# 04_LMS7002M_Misc.net
KiCad netlist of a schematic drawn in Altium Designer
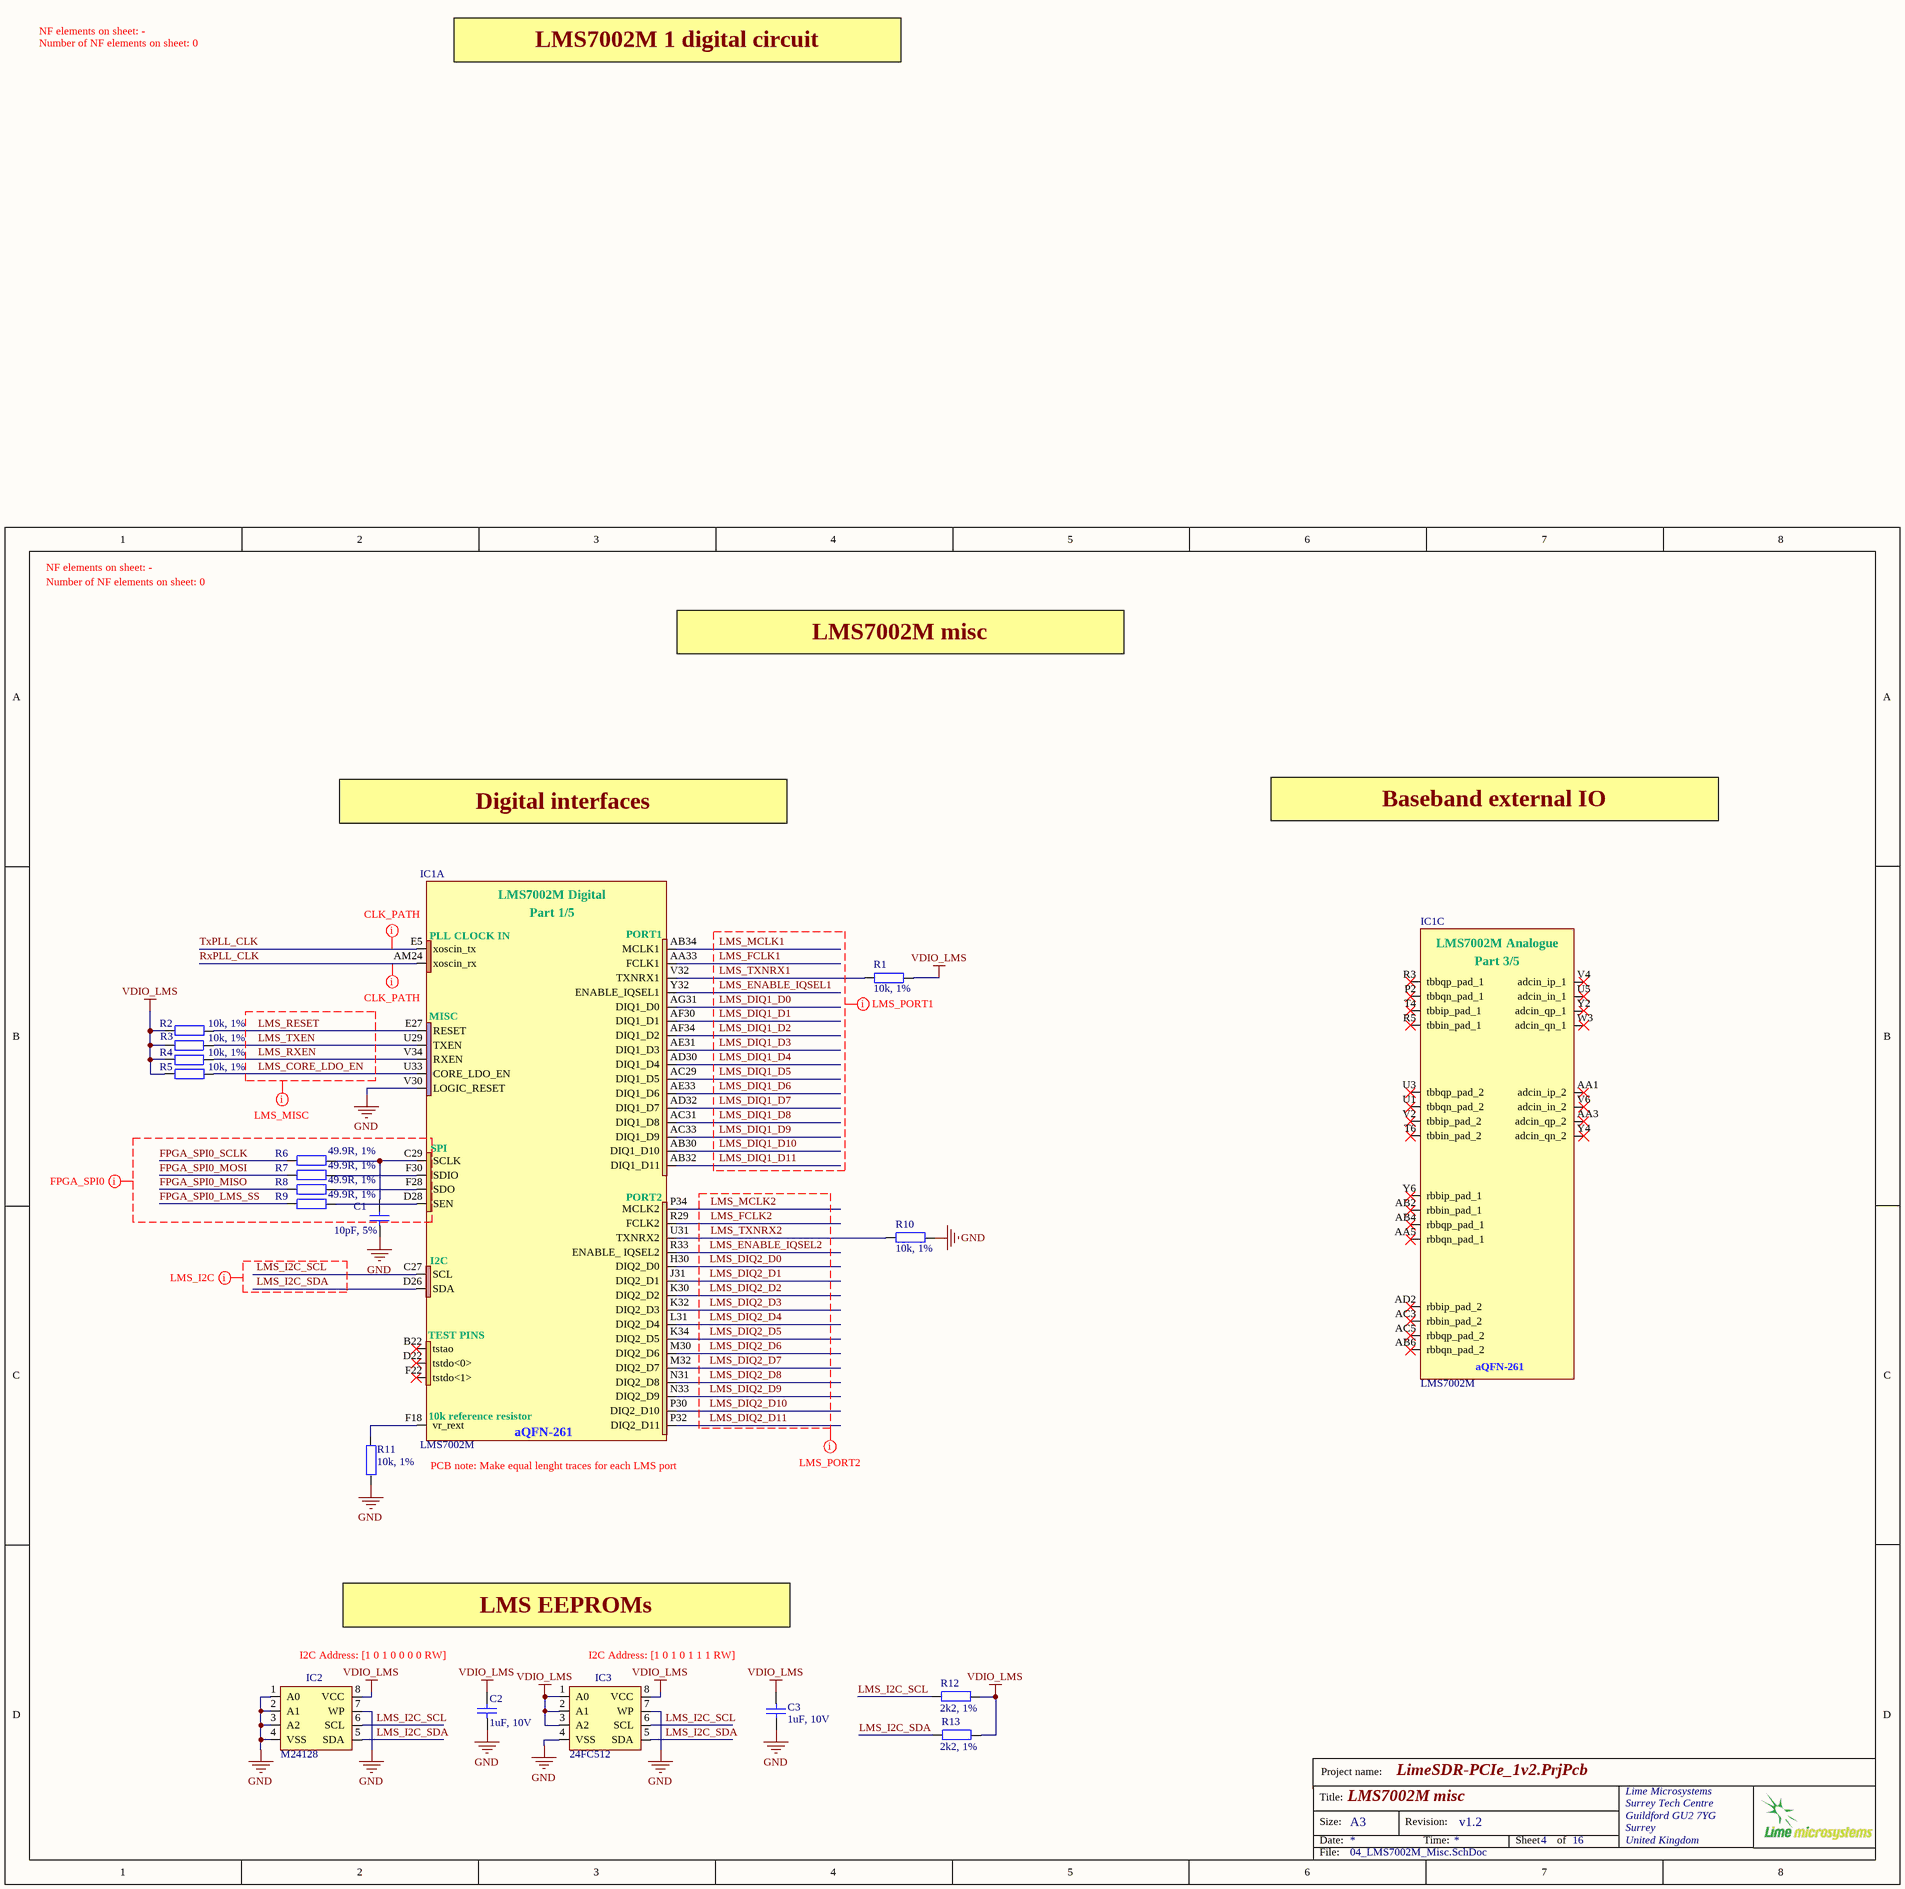
[diagram p0: 04_LMS7002M_Misc.SchDoc]

(export (version "E")
  (design (tool "Eeschema 10.0.6"))
  (components
    (comp (ref "C1")
      (value "10pF, 5%")
      (footprint "CAP0402")
      (fields (field (name "MANUFACTURER") "AVX"))
      (libsource (lib "LimeMicroAltiumLib_schLib") (part "Cap_0402"))
    )
    (comp (ref "C2")
      (value "1uF, 10V")
      (footprint "CAP0402")
      (fields (field (name "MANUFACTURER") "TDK"))
      (libsource (lib "LimeMicroAltiumLib_schLib") (part "Cap_0402"))
    )
    (comp (ref "C3")
      (value "1uF, 10V")
      (footprint "CAP0402")
      (fields (field (name "MANUFACTURER") "TDK"))
      (libsource (lib "LimeMicroAltiumLib_schLib") (part "Cap_0402"))
    )
    (comp (ref "IC1")
      (value "LMS7002M")
      (footprint "LMS7002M_v2")
      (fields (field (name "MANUFACTURER") "Lime Microsystems"))
      (libsource (lib "LimeMicroAltiumLib_schLib") (part "LMS7002M"))
    )
    (comp (ref "IC2")
      (value "M24128")
      (footprint "24FC512")
      (fields (field (name "MANUFACTURER") "STMicroelectronics"))
      (libsource (lib "LimeMicroAltiumLib_schLib") (part "24FC64F"))
    )
    (comp (ref "IC3")
      (value "24FC512")
      (footprint "24FC512")
      (fields (field (name "MANUFACTURER") "Microchip Technology"))
      (libsource (lib "LimeMicroAltiumLib_schLib") (part "24FC512"))
    )
    (comp (ref "R1")
      (value "10k, 1%")
      (footprint "RES0402")
      (fields (field (name "MANUFACTURER") "Yageo") (field (name "TOLERANCE") "±1%"))
      (libsource (lib "LimeMicroAltiumLib_schLib") (part "Res_0402"))
    )
    (comp (ref "R2")
      (value "10k, 1%")
      (footprint "RES0402")
      (fields (field (name "MANUFACTURER") "Yageo") (field (name "TOLERANCE") "±1%"))
      (libsource (lib "LimeMicroAltiumLib_schLib") (part "Res_0402"))
    )
    (comp (ref "R3")
      (value "10k, 1%")
      (footprint "RES0402")
      (fields (field (name "MANUFACTURER") "Yageo") (field (name "TOLERANCE") "±1%"))
      (libsource (lib "LimeMicroAltiumLib_schLib") (part "Res_0402"))
    )
    (comp (ref "R4")
      (value "10k, 1%")
      (footprint "RES0402")
      (fields (field (name "MANUFACTURER") "Yageo") (field (name "TOLERANCE") "±1%"))
      (libsource (lib "LimeMicroAltiumLib_schLib") (part "Res_0402"))
    )
    (comp (ref "R5")
      (value "10k, 1%")
      (footprint "RES0402")
      (fields (field (name "MANUFACTURER") "Yageo") (field (name "TOLERANCE") "±1%"))
      (libsource (lib "LimeMicroAltiumLib_schLib") (part "Res_0402"))
    )
    (comp (ref "R6")
      (value "49.9R, 1%")
      (footprint "RES0402")
      (fields
        (field (name "TOLERANCE") "±1%")
        (field (name "MANUFACTURER") "Samsung Electro-Mechanics America, Inc.")
        (field (name "MANUFACTURER PART NUMBER") "RC1005F49R9CS")
      )
      (libsource (lib "LimeMicroAltiumLib_schLib") (part "Res_0402"))
    )
    (comp (ref "R7")
      (value "49.9R, 1%")
      (footprint "RES0402")
      (fields
        (field (name "TOLERANCE") "±1%")
        (field (name "MANUFACTURER") "Samsung Electro-Mechanics America, Inc.")
        (field (name "MANUFACTURER PART NUMBER") "RC1005F49R9CS")
      )
      (libsource (lib "LimeMicroAltiumLib_schLib") (part "Res_0402"))
    )
    (comp (ref "R8")
      (value "49.9R, 1%")
      (footprint "RES0402")
      (fields
        (field (name "TOLERANCE") "±1%")
        (field (name "MANUFACTURER") "Samsung Electro-Mechanics America, Inc.")
        (field (name "MANUFACTURER PART NUMBER") "RC1005F49R9CS")
      )
      (libsource (lib "LimeMicroAltiumLib_schLib") (part "Res_0402"))
    )
    (comp (ref "R9")
      (value "49.9R, 1%")
      (footprint "RES0402")
      (fields
        (field (name "TOLERANCE") "±1%")
        (field (name "MANUFACTURER") "Samsung Electro-Mechanics America, Inc.")
        (field (name "MANUFACTURER PART NUMBER") "RC1005F49R9CS")
      )
      (libsource (lib "LimeMicroAltiumLib_schLib") (part "Res_0402"))
    )
    (comp (ref "R10")
      (value "10k, 1%")
      (footprint "RES0402")
      (fields (field (name "MANUFACTURER") "Yageo") (field (name "TOLERANCE") "±1%"))
      (libsource (lib "LimeMicroAltiumLib_schLib") (part "Res_0402"))
    )
    (comp (ref "R11")
      (value "10k, 1%")
      (footprint "RES0402")
      (fields (field (name "MANUFACTURER") "Yageo") (field (name "TOLERANCE") "±1%"))
      (libsource (lib "LimeMicroAltiumLib_schLib") (part "Res_0402"))
    )
    (comp (ref "R12")
      (value "2k2, 1%")
      (footprint "RES0402")
      (fields (field (name "MANUFACTURER") "Stackpole Electronics Inc") (field (name "TOLERANCE") "±1%"))
      (libsource (lib "LimeMicroAltiumLib_schLib") (part "Res_0402"))
    )
    (comp (ref "R13")
      (value "2k2, 1%")
      (footprint "RES0402")
      (fields (field (name "MANUFACTURER") "Stackpole Electronics Inc") (field (name "TOLERANCE") "±1%"))
      (libsource (lib "LimeMicroAltiumLib_schLib") (part "Res_0402"))
    )
  )
  (nets
    (net (code "1") (name "/FPGA_SPI0_LMS_SS") (class "Default")
      (node (ref "R9") (pin "2") (pinfunction "2_2") (pintype "passive"))
    )
    (net (code "2") (name "/FPGA_SPI0_MISO") (class "Default")
      (node (ref "R8") (pin "2") (pinfunction "2_2") (pintype "passive"))
    )
    (net (code "3") (name "/FPGA_SPI0_MOSI") (class "Default")
      (node (ref "R7") (pin "2") (pinfunction "2_2") (pintype "passive"))
    )
    (net (code "4") (name "/FPGA_SPI0_SCLK") (class "Default")
      (node (ref "R6") (pin "2") (pinfunction "2_2") (pintype "passive"))
    )
    (net (code "5") (name "/LMS_CORE_LDO_EN") (class "Default")
      (node (ref "IC1") (pin "U33") (pinfunction "CORE_LDO_EN_U33") (pintype "passive"))
      (node (ref "R5") (pin "1") (pinfunction "1_1") (pintype "passive"))
    )
    (net (code "6") (name "/LMS_DIQ1_D0") (class "Default")
      (node (ref "IC1") (pin "AG31") (pinfunction "DIQ1_D0_AG31") (pintype "passive"))
    )
    (net (code "7") (name "/LMS_DIQ1_D1") (class "Default")
      (node (ref "IC1") (pin "AF30") (pinfunction "DIQ1_D1_AF30") (pintype "passive"))
    )
    (net (code "8") (name "/LMS_DIQ1_D2") (class "Default")
      (node (ref "IC1") (pin "AF34") (pinfunction "DIQ1_D2_AF34") (pintype "passive"))
    )
    (net (code "9") (name "/LMS_DIQ1_D3") (class "Default")
      (node (ref "IC1") (pin "AE31") (pinfunction "DIQ1_D3_AE31") (pintype "passive"))
    )
    (net (code "10") (name "/LMS_DIQ1_D4") (class "Default")
      (node (ref "IC1") (pin "AD30") (pinfunction "DIQ1_D4_AD30") (pintype "passive"))
    )
    (net (code "11") (name "/LMS_DIQ1_D5") (class "Default")
      (node (ref "IC1") (pin "AC29") (pinfunction "DIQ1_D5_AC29") (pintype "passive"))
    )
    (net (code "12") (name "/LMS_DIQ1_D6") (class "Default")
      (node (ref "IC1") (pin "AE33") (pinfunction "DIQ1_D6_AE33") (pintype "passive"))
    )
    (net (code "13") (name "/LMS_DIQ1_D7") (class "Default")
      (node (ref "IC1") (pin "AD32") (pinfunction "DIQ1_D7_AD32") (pintype "passive"))
    )
    (net (code "14") (name "/LMS_DIQ1_D8") (class "Default")
      (node (ref "IC1") (pin "AC31") (pinfunction "DIQ1_D8_AC31") (pintype "passive"))
    )
    (net (code "15") (name "/LMS_DIQ1_D9") (class "Default")
      (node (ref "IC1") (pin "AC33") (pinfunction "DIQ1_D9_AC33") (pintype "passive"))
    )
    (net (code "16") (name "/LMS_DIQ1_D10") (class "Default")
      (node (ref "IC1") (pin "AB30") (pinfunction "DIQ1_D10_AB30") (pintype "passive"))
    )
    (net (code "17") (name "/LMS_DIQ1_D11") (class "Default")
      (node (ref "IC1") (pin "AB32") (pinfunction "DIQ1_D11_AB32") (pintype "passive"))
    )
    (net (code "18") (name "/LMS_DIQ2_D0") (class "Default")
      (node (ref "IC1") (pin "H30") (pinfunction "DIQ2_D0_H30") (pintype "passive"))
    )
    (net (code "19") (name "/LMS_DIQ2_D1") (class "Default")
      (node (ref "IC1") (pin "J31") (pinfunction "DIQ2_D1_J31") (pintype "passive"))
    )
    (net (code "20") (name "/LMS_DIQ2_D2") (class "Default")
      (node (ref "IC1") (pin "K30") (pinfunction "DIQ2_D2_K30") (pintype "passive"))
    )
    (net (code "21") (name "/LMS_DIQ2_D3") (class "Default")
      (node (ref "IC1") (pin "K32") (pinfunction "DIQ2_D3_K32") (pintype "passive"))
    )
    (net (code "22") (name "/LMS_DIQ2_D4") (class "Default")
      (node (ref "IC1") (pin "L31") (pinfunction "DIQ2_D4_L31") (pintype "passive"))
    )
    (net (code "23") (name "/LMS_DIQ2_D5") (class "Default")
      (node (ref "IC1") (pin "K34") (pinfunction "DIQ2_D5_K34") (pintype "passive"))
    )
    (net (code "24") (name "/LMS_DIQ2_D6") (class "Default")
      (node (ref "IC1") (pin "M30") (pinfunction "DIQ2_D6_M30") (pintype "passive"))
    )
    (net (code "25") (name "/LMS_DIQ2_D7") (class "Default")
      (node (ref "IC1") (pin "M32") (pinfunction "DIQ2_D7_M32") (pintype "passive"))
    )
    (net (code "26") (name "/LMS_DIQ2_D8") (class "Default")
      (node (ref "IC1") (pin "N31") (pinfunction "DIQ2_D8_N31") (pintype "passive"))
    )
    (net (code "27") (name "/LMS_DIQ2_D9") (class "Default")
      (node (ref "IC1") (pin "N33") (pinfunction "DIQ2_D9_N33") (pintype "passive"))
    )
    (net (code "28") (name "/LMS_DIQ2_D10") (class "Default")
      (node (ref "IC1") (pin "P30") (pinfunction "DIQ2_D10_P30") (pintype "passive"))
    )
    (net (code "29") (name "/LMS_DIQ2_D11") (class "Default")
      (node (ref "IC1") (pin "P32") (pinfunction "DIQ2_D11_P32") (pintype "passive"))
    )
    (net (code "30") (name "/LMS_ENABLE_IQSEL1") (class "Default")
      (node (ref "IC1") (pin "Y32") (pinfunction "ENABLE_IQSEL1_Y32") (pintype "passive"))
    )
    (net (code "31") (name "/LMS_ENABLE_IQSEL2") (class "Default")
      (node (ref "IC1") (pin "R33") (pinfunction "ENABLE__IQSEL2_R33") (pintype "passive"))
    )
    (net (code "32") (name "/LMS_FCLK1") (class "Default")
      (node (ref "IC1") (pin "AA33") (pinfunction "FCLK1_AA33") (pintype "passive"))
    )
    (net (code "33") (name "/LMS_FCLK2") (class "Default")
      (node (ref "IC1") (pin "R29") (pinfunction "FCLK2_R29") (pintype "passive"))
    )
    (net (code "34") (name "/LMS_I2C_SCL") (class "Default")
      (node (ref "IC1") (pin "C27") (pinfunction "SCL_C27") (pintype "passive"))
      (node (ref "IC2") (pin "6") (pinfunction "SCL_6") (pintype "passive"))
      (node (ref "IC3") (pin "6") (pinfunction "SCL_6") (pintype "passive"))
      (node (ref "R12") (pin "2") (pinfunction "2_2") (pintype "passive"))
    )
    (net (code "35") (name "/LMS_I2C_SDA") (class "Default")
      (node (ref "IC1") (pin "D26") (pinfunction "SDA_D26") (pintype "passive"))
      (node (ref "IC2") (pin "5") (pinfunction "SDA_5") (pintype "passive"))
      (node (ref "IC3") (pin "5") (pinfunction "SDA_5") (pintype "passive"))
      (node (ref "R13") (pin "2") (pinfunction "2_2") (pintype "passive"))
    )
    (net (code "36") (name "/LMS_MCLK1") (class "Default")
      (node (ref "IC1") (pin "AB34") (pinfunction "MCLK1_AB34") (pintype "passive"))
    )
    (net (code "37") (name "/LMS_MCLK2") (class "Default")
      (node (ref "IC1") (pin "P34") (pinfunction "MCLK2_P34") (pintype "passive"))
    )
    (net (code "38") (name "/LMS_RESET") (class "Default")
      (node (ref "IC1") (pin "E27") (pinfunction "RESET_E27") (pintype "passive"))
      (node (ref "R2") (pin "1") (pinfunction "1_1") (pintype "passive"))
    )
    (net (code "39") (name "/LMS_RXEN") (class "Default")
      (node (ref "IC1") (pin "V34") (pinfunction "RXEN_V34") (pintype "passive"))
      (node (ref "R4") (pin "2") (pinfunction "2_2") (pintype "passive"))
    )
    (net (code "40") (name "/LMS_TXEN") (class "Default")
      (node (ref "IC1") (pin "U29") (pinfunction "TXEN_U29") (pintype "passive"))
      (node (ref "R3") (pin "2") (pinfunction "2_2") (pintype "passive"))
    )
    (net (code "41") (name "/LMS_TXNRX1") (class "Default")
      (node (ref "IC1") (pin "V32") (pinfunction "TXNRX1_V32") (pintype "passive"))
      (node (ref "R1") (pin "1") (pinfunction "1_1") (pintype "passive"))
    )
    (net (code "42") (name "/LMS_TXNRX2") (class "Default")
      (node (ref "IC1") (pin "U31") (pinfunction "TXNRX2_U31") (pintype "passive"))
      (node (ref "R10") (pin "2") (pinfunction "2_2") (pintype "passive"))
    )
    (net (code "43") (name "/RxPLL_CLK") (class "Default")
      (node (ref "IC1") (pin "AM24") (pinfunction "xoscin_rx_AM24") (pintype "passive"))
    )
    (net (code "44") (name "/TxPLL_CLK") (class "Default")
      (node (ref "IC1") (pin "E5") (pinfunction "xoscin_tx_E5") (pintype "passive"))
    )
    (net (code "45") (name "GND") (class "Default")
      (node (ref "C1") (pin "2") (pinfunction "2_2") (pintype "passive"))
      (node (ref "C2") (pin "2") (pinfunction "2_2") (pintype "passive"))
      (node (ref "C3") (pin "1") (pinfunction "1_1") (pintype "passive"))
      (node (ref "IC1") (pin "V30") (pinfunction "LOGIC_RESET_V30") (pintype "passive"))
      (node (ref "IC2") (pin "1") (pinfunction "A0_1") (pintype "passive"))
      (node (ref "IC2") (pin "2") (pinfunction "A1_2") (pintype "passive"))
      (node (ref "IC2") (pin "3") (pinfunction "A2_3") (pintype "passive"))
      (node (ref "IC2") (pin "4") (pinfunction "VSS_4") (pintype "passive"))
      (node (ref "IC2") (pin "7") (pinfunction "WP_7") (pintype "passive"))
      (node (ref "IC3") (pin "4") (pinfunction "VSS_4") (pintype "passive"))
      (node (ref "IC3") (pin "7") (pinfunction "WP_7") (pintype "passive"))
      (node (ref "R10") (pin "1") (pinfunction "1_1") (pintype "passive"))
      (node (ref "R11") (pin "2") (pinfunction "2_2") (pintype "passive"))
    )
    (net (code "46") (name "Net-(IC1A-SCLK)") (class "Default")
      (node (ref "C1") (pin "1") (pinfunction "1_1") (pintype "passive"))
      (node (ref "IC1") (pin "C29") (pinfunction "SCLK_C29") (pintype "passive"))
      (node (ref "R6") (pin "1") (pinfunction "1_1") (pintype "passive"))
    )
    (net (code "47") (name "Net-(IC1A-SDIO)") (class "Default")
      (node (ref "IC1") (pin "F30") (pinfunction "SDIO_F30") (pintype "passive"))
      (node (ref "R7") (pin "1") (pinfunction "1_1") (pintype "passive"))
    )
    (net (code "48") (name "Net-(IC1A-SDO)") (class "Default")
      (node (ref "IC1") (pin "F28") (pinfunction "SDO_F28") (pintype "passive"))
      (node (ref "R8") (pin "1") (pinfunction "1_1") (pintype "passive"))
    )
    (net (code "49") (name "Net-(IC1A-SEN)") (class "Default")
      (node (ref "IC1") (pin "D28") (pinfunction "SEN_D28") (pintype "passive"))
      (node (ref "R9") (pin "1") (pinfunction "1_1") (pintype "passive"))
    )
    (net (code "50") (name "Net-(IC1A-vr_rext)") (class "Default")
      (node (ref "IC1") (pin "F18") (pinfunction "vr_rext_F18") (pintype "passive"))
      (node (ref "R11") (pin "1") (pinfunction "1_1") (pintype "passive"))
    )
    (net (code "51") (name "VDIO_LMS") (class "Default")
      (node (ref "C2") (pin "1") (pinfunction "1_1") (pintype "passive"))
      (node (ref "C3") (pin "2") (pinfunction "2_2") (pintype "passive"))
      (node (ref "IC2") (pin "8") (pinfunction "VCC_8") (pintype "passive"))
      (node (ref "IC3") (pin "1") (pinfunction "A0_1") (pintype "passive"))
      (node (ref "IC3") (pin "2") (pinfunction "A1_2") (pintype "passive"))
      (node (ref "IC3") (pin "3") (pinfunction "A2_3") (pintype "passive"))
      (node (ref "IC3") (pin "8") (pinfunction "VCC_8") (pintype "passive"))
      (node (ref "R1") (pin "2") (pinfunction "2_2") (pintype "passive"))
      (node (ref "R12") (pin "1") (pinfunction "1_1") (pintype "passive"))
      (node (ref "R13") (pin "1") (pinfunction "1_1") (pintype "passive"))
      (node (ref "R2") (pin "2") (pinfunction "2_2") (pintype "passive"))
      (node (ref "R3") (pin "1") (pinfunction "1_1") (pintype "passive"))
      (node (ref "R4") (pin "1") (pinfunction "1_1") (pintype "passive"))
      (node (ref "R5") (pin "2") (pinfunction "2_2") (pintype "passive"))
    )
    (net (code "52") (name "unconnected-(IC1A-tstao-PadB22)") (class "Default")
      (node (ref "IC1") (pin "B22") (pinfunction "tstao_B22") (pintype "passive+no_connect"))
    )
    (net (code "53") (name "unconnected-(IC1A-tstdo<0>-PadD22)") (class "Default")
      (node (ref "IC1") (pin "D22") (pinfunction "tstdo<0>_D22") (pintype "passive+no_connect"))
    )
    (net (code "54") (name "unconnected-(IC1A-tstdo<1>-PadF22)") (class "Default")
      (node (ref "IC1") (pin "F22") (pinfunction "tstdo<1>_F22") (pintype "passive+no_connect"))
    )
    (net (code "55") (name "unconnected-(IC1C-adcin_in_1-PadU5)") (class "Default")
      (node (ref "IC1") (pin "U5") (pinfunction "adcin_in_1_U5") (pintype "passive+no_connect"))
    )
    (net (code "56") (name "unconnected-(IC1C-adcin_in_2-PadV6)") (class "Default")
      (node (ref "IC1") (pin "V6") (pinfunction "adcin_in_2_V6") (pintype "passive+no_connect"))
    )
    (net (code "57") (name "unconnected-(IC1C-adcin_ip_1-PadV4)") (class "Default")
      (node (ref "IC1") (pin "V4") (pinfunction "adcin_ip_1_V4") (pintype "passive+no_connect"))
    )
    (net (code "58") (name "unconnected-(IC1C-adcin_ip_2-PadAA1)") (class "Default")
      (node (ref "IC1") (pin "AA1") (pinfunction "adcin_ip_2_AA1") (pintype "passive+no_connect"))
    )
    (net (code "59") (name "unconnected-(IC1C-adcin_qn_1-PadW3)") (class "Default")
      (node (ref "IC1") (pin "W3") (pinfunction "adcin_qn_1_W3") (pintype "passive+no_connect"))
    )
    (net (code "60") (name "unconnected-(IC1C-adcin_qn_2-PadY4)") (class "Default")
      (node (ref "IC1") (pin "Y4") (pinfunction "adcin_qn_2_Y4") (pintype "passive+no_connect"))
    )
    (net (code "61") (name "unconnected-(IC1C-adcin_qp_1-PadY2)") (class "Default")
      (node (ref "IC1") (pin "Y2") (pinfunction "adcin_qp_1_Y2") (pintype "passive+no_connect"))
    )
    (net (code "62") (name "unconnected-(IC1C-adcin_qp_2-PadAA3)") (class "Default")
      (node (ref "IC1") (pin "AA3") (pinfunction "adcin_qp_2_AA3") (pintype "passive+no_connect"))
    )
    (net (code "63") (name "unconnected-(IC1C-rbbin_pad_1-PadAB2)") (class "Default")
      (node (ref "IC1") (pin "AB2") (pinfunction "rbbin_pad_1_AB2") (pintype "passive+no_connect"))
    )
    (net (code "64") (name "unconnected-(IC1C-rbbin_pad_2-PadAC3)") (class "Default")
      (node (ref "IC1") (pin "AC3") (pinfunction "rbbin_pad_2_AC3") (pintype "passive+no_connect"))
    )
    (net (code "65") (name "unconnected-(IC1C-rbbip_pad_1-PadY6)") (class "Default")
      (node (ref "IC1") (pin "Y6") (pinfunction "rbbip_pad_1_Y6") (pintype "passive+no_connect"))
    )
    (net (code "66") (name "unconnected-(IC1C-rbbip_pad_2-PadAD2)") (class "Default")
      (node (ref "IC1") (pin "AD2") (pinfunction "rbbip_pad_2_AD2") (pintype "passive+no_connect"))
    )
    (net (code "67") (name "unconnected-(IC1C-rbbqn_pad_1-PadAA5)") (class "Default")
      (node (ref "IC1") (pin "AA5") (pinfunction "rbbqn_pad_1_AA5") (pintype "passive+no_connect"))
    )
    (net (code "68") (name "unconnected-(IC1C-rbbqn_pad_2-PadAB6)") (class "Default")
      (node (ref "IC1") (pin "AB6") (pinfunction "rbbqn_pad_2_AB6") (pintype "passive+no_connect"))
    )
    (net (code "69") (name "unconnected-(IC1C-rbbqp_pad_1-PadAB4)") (class "Default")
      (node (ref "IC1") (pin "AB4") (pinfunction "rbbqp_pad_1_AB4") (pintype "passive+no_connect"))
    )
    (net (code "70") (name "unconnected-(IC1C-rbbqp_pad_2-PadAC5)") (class "Default")
      (node (ref "IC1") (pin "AC5") (pinfunction "rbbqp_pad_2_AC5") (pintype "passive+no_connect"))
    )
    (net (code "71") (name "unconnected-(IC1C-tbbin_pad_1-PadR5)") (class "Default")
      (node (ref "IC1") (pin "R5") (pinfunction "tbbin_pad_1_R5") (pintype "passive+no_connect"))
    )
    (net (code "72") (name "unconnected-(IC1C-tbbin_pad_2-PadT6)") (class "Default")
      (node (ref "IC1") (pin "T6") (pinfunction "tbbin_pad_2_T6") (pintype "passive+no_connect"))
    )
    (net (code "73") (name "unconnected-(IC1C-tbbip_pad_1-PadT4)") (class "Default")
      (node (ref "IC1") (pin "T4") (pinfunction "tbbip_pad_1_T4") (pintype "passive+no_connect"))
    )
    (net (code "74") (name "unconnected-(IC1C-tbbip_pad_2-PadV2)") (class "Default")
      (node (ref "IC1") (pin "V2") (pinfunction "tbbip_pad_2_V2") (pintype "passive+no_connect"))
    )
    (net (code "75") (name "unconnected-(IC1C-tbbqn_pad_1-PadP2)") (class "Default")
      (node (ref "IC1") (pin "P2") (pinfunction "tbbqn_pad_1_P2") (pintype "passive+no_connect"))
    )
    (net (code "76") (name "unconnected-(IC1C-tbbqn_pad_2-PadU1)") (class "Default")
      (node (ref "IC1") (pin "U1") (pinfunction "tbbqn_pad_2_U1") (pintype "passive+no_connect"))
    )
    (net (code "77") (name "unconnected-(IC1C-tbbqp_pad_1-PadR3)") (class "Default")
      (node (ref "IC1") (pin "R3") (pinfunction "tbbqp_pad_1_R3") (pintype "passive+no_connect"))
    )
    (net (code "78") (name "unconnected-(IC1C-tbbqp_pad_2-PadU3)") (class "Default")
      (node (ref "IC1") (pin "U3") (pinfunction "tbbqp_pad_2_U3") (pintype "passive+no_connect"))
    )
  )
)
